# Dual6x09_CoCo2.net
KiCad netlist of a schematic drawn in EAGLE
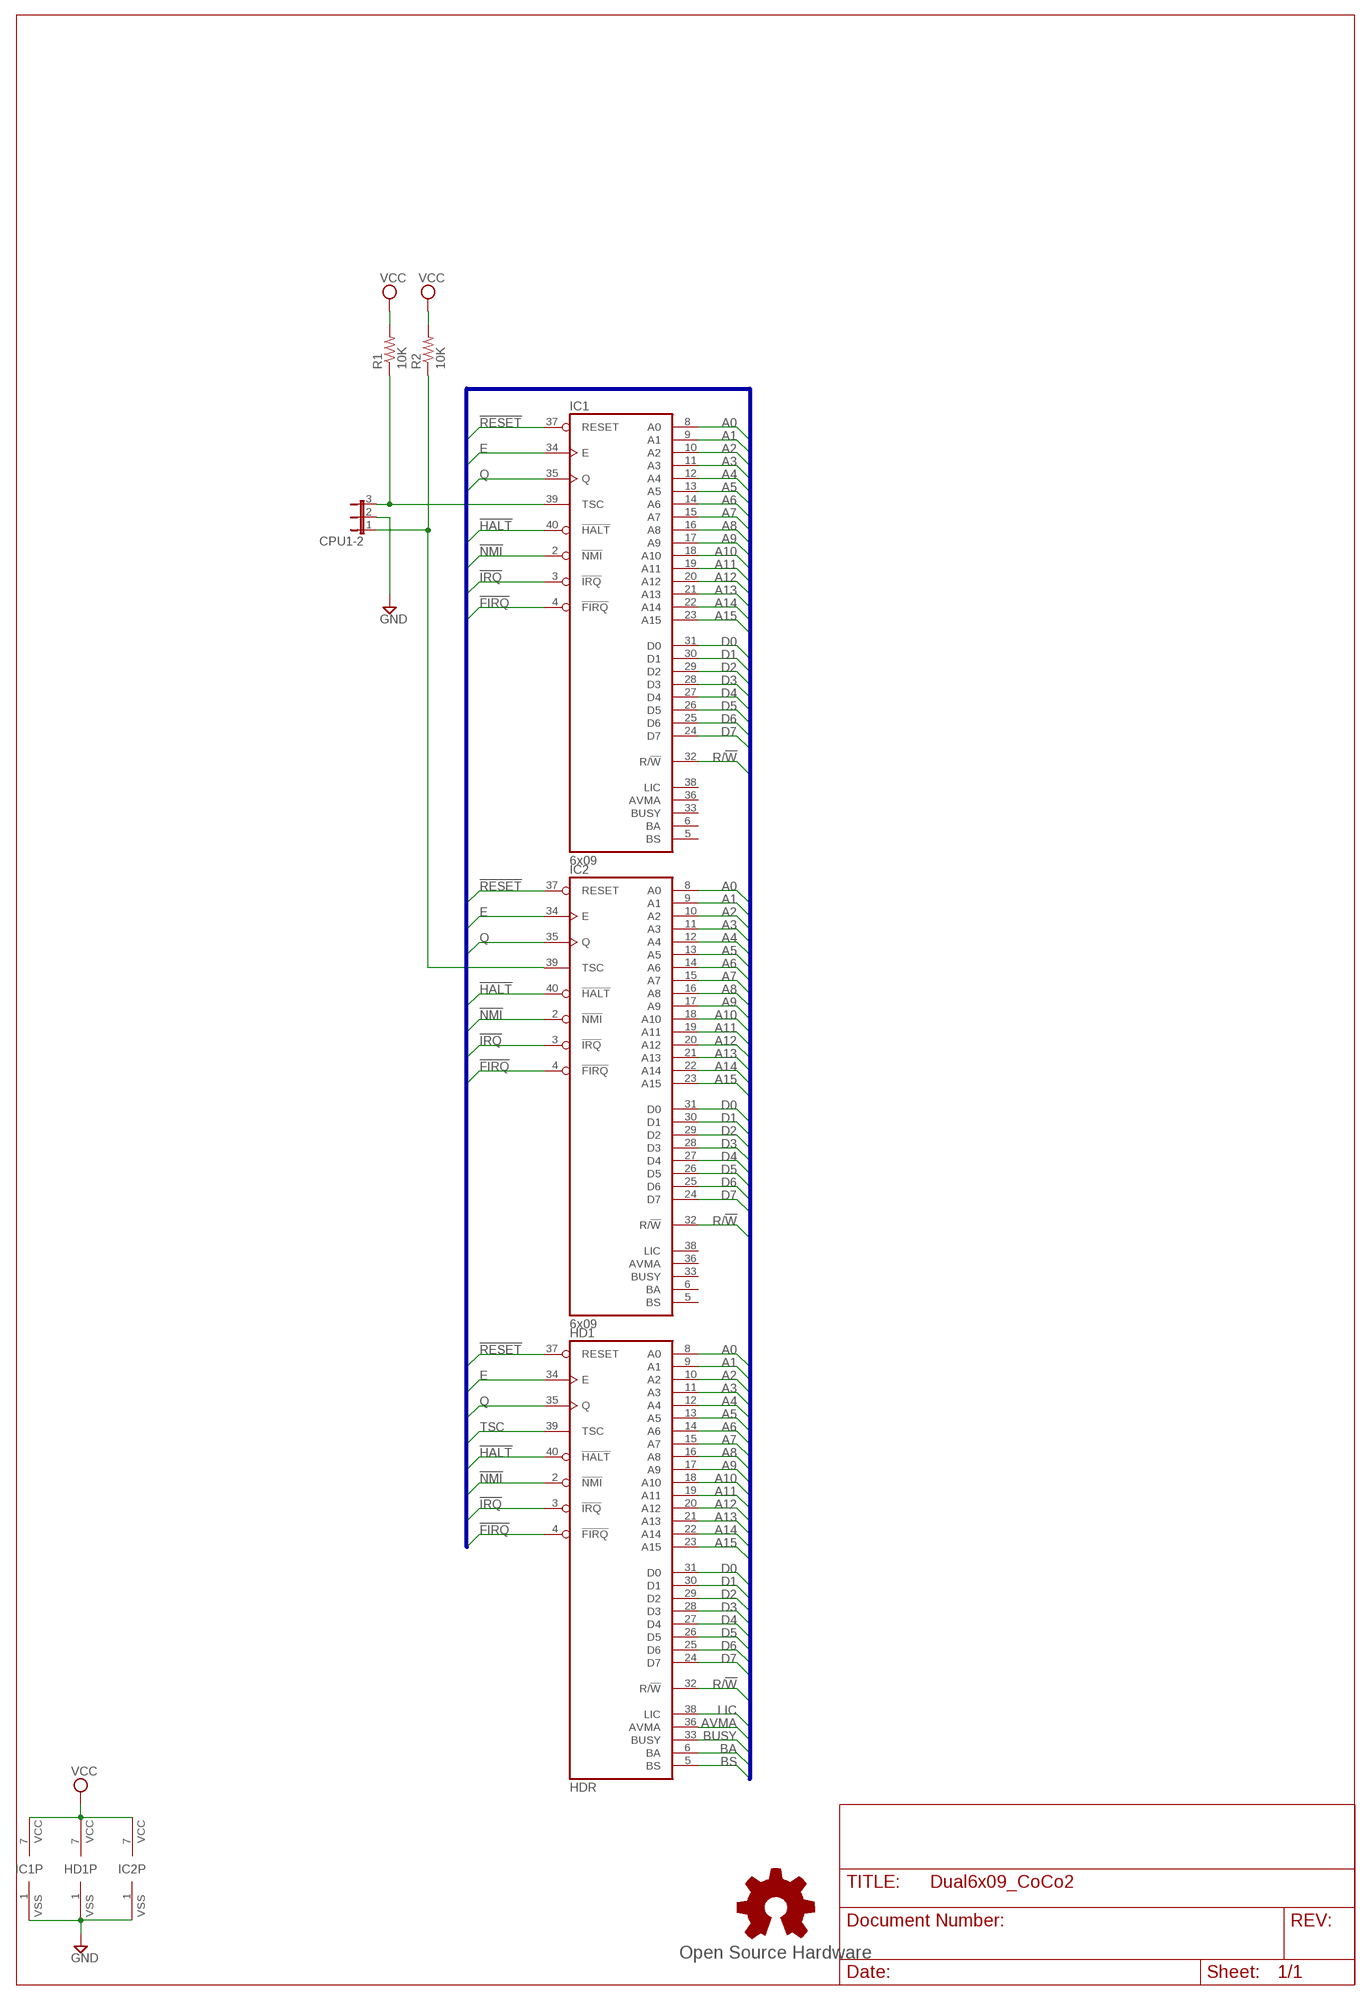
[diagram p0: schematic, sheet 1]

(export (version "E")
  (design (tool "Eeschema 10.0.6"))
  (components
    (comp (ref "CPU1-2")
      (value "JP2E")
      (footprint "eagle-import:JP2")
      (libsource (lib "eagle-import") (part "JP2E"))
    )
    (comp (ref "GOLD_ORB_SM1")
      (value "Open Source Hardware")
      (footprint "eagle-import:OSHW_5MM")
      (libsource (lib "eagle-import") (part "OSHWLOGOLOGO5MM"))
    )
    (comp (ref "HD1")
      (value "HDR")
      (footprint "eagle-import:DIL40-ROUNDPAD")
      (libsource (lib "eagle-import") (part "MC6809ER"))
    )
    (comp (ref "IC1")
      (value "6x09")
      (footprint "eagle-import:DIL40-ROUNDPAD")
      (libsource (lib "eagle-import") (part "MC6809ER"))
    )
    (comp (ref "IC2")
      (value "6x09")
      (footprint "eagle-import:DIL40-ROUNDPAD")
      (libsource (lib "eagle-import") (part "MC6809ER"))
    )
    (comp (ref "R1")
      (value "10K")
      (footprint "eagle-import:0204V")
      (libsource (lib "eagle-import") (part "R-US_0204/2V"))
    )
    (comp (ref "R2")
      (value "10K")
      (footprint "eagle-import:0204V")
      (libsource (lib "eagle-import") (part "R-US_0204/2V"))
    )
  )
  (nets
    (net (code "1") (name "/A0") (class "Default")
      (node (ref "HD1") (pin "8") (pinfunction "A0_8") (pintype "tri_state"))
      (node (ref "IC1") (pin "8") (pinfunction "A0_8") (pintype "tri_state"))
      (node (ref "IC2") (pin "8") (pinfunction "A0_8") (pintype "tri_state"))
    )
    (net (code "2") (name "/A1") (class "Default")
      (node (ref "HD1") (pin "9") (pinfunction "A1_9") (pintype "tri_state"))
      (node (ref "IC1") (pin "9") (pinfunction "A1_9") (pintype "tri_state"))
      (node (ref "IC2") (pin "9") (pinfunction "A1_9") (pintype "tri_state"))
    )
    (net (code "3") (name "/A2") (class "Default")
      (node (ref "HD1") (pin "10") (pinfunction "A2_10") (pintype "tri_state"))
      (node (ref "IC1") (pin "10") (pinfunction "A2_10") (pintype "tri_state"))
      (node (ref "IC2") (pin "10") (pinfunction "A2_10") (pintype "tri_state"))
    )
    (net (code "4") (name "/A3") (class "Default")
      (node (ref "HD1") (pin "11") (pinfunction "A3_11") (pintype "tri_state"))
      (node (ref "IC1") (pin "11") (pinfunction "A3_11") (pintype "tri_state"))
      (node (ref "IC2") (pin "11") (pinfunction "A3_11") (pintype "tri_state"))
    )
    (net (code "5") (name "/A4") (class "Default")
      (node (ref "HD1") (pin "12") (pinfunction "A4_12") (pintype "tri_state"))
      (node (ref "IC1") (pin "12") (pinfunction "A4_12") (pintype "tri_state"))
      (node (ref "IC2") (pin "12") (pinfunction "A4_12") (pintype "tri_state"))
    )
    (net (code "6") (name "/A5") (class "Default")
      (node (ref "HD1") (pin "13") (pinfunction "A5_13") (pintype "tri_state"))
      (node (ref "IC1") (pin "13") (pinfunction "A5_13") (pintype "tri_state"))
      (node (ref "IC2") (pin "13") (pinfunction "A5_13") (pintype "tri_state"))
    )
    (net (code "7") (name "/A6") (class "Default")
      (node (ref "HD1") (pin "14") (pinfunction "A6_14") (pintype "tri_state"))
      (node (ref "IC1") (pin "14") (pinfunction "A6_14") (pintype "tri_state"))
      (node (ref "IC2") (pin "14") (pinfunction "A6_14") (pintype "tri_state"))
    )
    (net (code "8") (name "/A7") (class "Default")
      (node (ref "HD1") (pin "15") (pinfunction "A7_15") (pintype "tri_state"))
      (node (ref "IC1") (pin "15") (pinfunction "A7_15") (pintype "tri_state"))
      (node (ref "IC2") (pin "15") (pinfunction "A7_15") (pintype "tri_state"))
    )
    (net (code "9") (name "/A8") (class "Default")
      (node (ref "HD1") (pin "16") (pinfunction "A8_16") (pintype "tri_state"))
      (node (ref "IC1") (pin "16") (pinfunction "A8_16") (pintype "tri_state"))
      (node (ref "IC2") (pin "16") (pinfunction "A8_16") (pintype "tri_state"))
    )
    (net (code "10") (name "/A9") (class "Default")
      (node (ref "HD1") (pin "17") (pinfunction "A9_17") (pintype "tri_state"))
      (node (ref "IC1") (pin "17") (pinfunction "A9_17") (pintype "tri_state"))
      (node (ref "IC2") (pin "17") (pinfunction "A9_17") (pintype "tri_state"))
    )
    (net (code "11") (name "/A10") (class "Default")
      (node (ref "HD1") (pin "18") (pinfunction "A10_18") (pintype "tri_state"))
      (node (ref "IC1") (pin "18") (pinfunction "A10_18") (pintype "tri_state"))
      (node (ref "IC2") (pin "18") (pinfunction "A10_18") (pintype "tri_state"))
    )
    (net (code "12") (name "/A11") (class "Default")
      (node (ref "HD1") (pin "19") (pinfunction "A11_19") (pintype "tri_state"))
      (node (ref "IC1") (pin "19") (pinfunction "A11_19") (pintype "tri_state"))
      (node (ref "IC2") (pin "19") (pinfunction "A11_19") (pintype "tri_state"))
    )
    (net (code "13") (name "/A12") (class "Default")
      (node (ref "HD1") (pin "20") (pinfunction "A12_20") (pintype "tri_state"))
      (node (ref "IC1") (pin "20") (pinfunction "A12_20") (pintype "tri_state"))
      (node (ref "IC2") (pin "20") (pinfunction "A12_20") (pintype "tri_state"))
    )
    (net (code "14") (name "/A13") (class "Default")
      (node (ref "HD1") (pin "21") (pinfunction "A13_21") (pintype "tri_state"))
      (node (ref "IC1") (pin "21") (pinfunction "A13_21") (pintype "tri_state"))
      (node (ref "IC2") (pin "21") (pinfunction "A13_21") (pintype "tri_state"))
    )
    (net (code "15") (name "/A14") (class "Default")
      (node (ref "HD1") (pin "22") (pinfunction "A14_22") (pintype "tri_state"))
      (node (ref "IC1") (pin "22") (pinfunction "A14_22") (pintype "tri_state"))
      (node (ref "IC2") (pin "22") (pinfunction "A14_22") (pintype "tri_state"))
    )
    (net (code "16") (name "/A15") (class "Default")
      (node (ref "HD1") (pin "23") (pinfunction "A15_23") (pintype "tri_state"))
      (node (ref "IC1") (pin "23") (pinfunction "A15_23") (pintype "tri_state"))
      (node (ref "IC2") (pin "23") (pinfunction "A15_23") (pintype "tri_state"))
    )
    (net (code "17") (name "/AVMA") (class "Default")
      (node (ref "HD1") (pin "36") (pinfunction "AVMA_36") (pintype "output"))
    )
    (net (code "18") (name "/BA") (class "Default")
      (node (ref "HD1") (pin "6") (pinfunction "BA_6") (pintype "output"))
    )
    (net (code "19") (name "/BS") (class "Default")
      (node (ref "HD1") (pin "5") (pinfunction "BS_5") (pintype "output"))
    )
    (net (code "20") (name "/BUSY") (class "Default")
      (node (ref "HD1") (pin "33") (pinfunction "BUSY_33") (pintype "output"))
    )
    (net (code "21") (name "/D0") (class "Default")
      (node (ref "HD1") (pin "31") (pinfunction "D0_31") (pintype "bidirectional"))
      (node (ref "IC1") (pin "31") (pinfunction "D0_31") (pintype "bidirectional"))
      (node (ref "IC2") (pin "31") (pinfunction "D0_31") (pintype "bidirectional"))
    )
    (net (code "22") (name "/D1") (class "Default")
      (node (ref "HD1") (pin "30") (pinfunction "D1_30") (pintype "bidirectional"))
      (node (ref "IC1") (pin "30") (pinfunction "D1_30") (pintype "bidirectional"))
      (node (ref "IC2") (pin "30") (pinfunction "D1_30") (pintype "bidirectional"))
    )
    (net (code "23") (name "/D2") (class "Default")
      (node (ref "HD1") (pin "29") (pinfunction "D2_29") (pintype "bidirectional"))
      (node (ref "IC1") (pin "29") (pinfunction "D2_29") (pintype "bidirectional"))
      (node (ref "IC2") (pin "29") (pinfunction "D2_29") (pintype "bidirectional"))
    )
    (net (code "24") (name "/D3") (class "Default")
      (node (ref "HD1") (pin "28") (pinfunction "D3_28") (pintype "bidirectional"))
      (node (ref "IC1") (pin "28") (pinfunction "D3_28") (pintype "bidirectional"))
      (node (ref "IC2") (pin "28") (pinfunction "D3_28") (pintype "bidirectional"))
    )
    (net (code "25") (name "/D4") (class "Default")
      (node (ref "HD1") (pin "27") (pinfunction "D4_27") (pintype "bidirectional"))
      (node (ref "IC1") (pin "27") (pinfunction "D4_27") (pintype "bidirectional"))
      (node (ref "IC2") (pin "27") (pinfunction "D4_27") (pintype "bidirectional"))
    )
    (net (code "26") (name "/D5") (class "Default")
      (node (ref "HD1") (pin "26") (pinfunction "D5_26") (pintype "bidirectional"))
      (node (ref "IC1") (pin "26") (pinfunction "D5_26") (pintype "bidirectional"))
      (node (ref "IC2") (pin "26") (pinfunction "D5_26") (pintype "bidirectional"))
    )
    (net (code "27") (name "/D6") (class "Default")
      (node (ref "HD1") (pin "25") (pinfunction "D6_25") (pintype "bidirectional"))
      (node (ref "IC1") (pin "25") (pinfunction "D6_25") (pintype "bidirectional"))
      (node (ref "IC2") (pin "25") (pinfunction "D6_25") (pintype "bidirectional"))
    )
    (net (code "28") (name "/D7") (class "Default")
      (node (ref "HD1") (pin "24") (pinfunction "D7_24") (pintype "bidirectional"))
      (node (ref "IC1") (pin "24") (pinfunction "D7_24") (pintype "bidirectional"))
      (node (ref "IC2") (pin "24") (pinfunction "D7_24") (pintype "bidirectional"))
    )
    (net (code "29") (name "/E") (class "Default")
      (node (ref "HD1") (pin "34") (pinfunction "E_34") (pintype "input"))
      (node (ref "IC1") (pin "34") (pinfunction "E_34") (pintype "input"))
      (node (ref "IC2") (pin "34") (pinfunction "E_34") (pintype "input"))
    )
    (net (code "30") (name "/LIC") (class "Default")
      (node (ref "HD1") (pin "38") (pinfunction "LIC_38") (pintype "output"))
    )
    (net (code "31") (name "/Q") (class "Default")
      (node (ref "HD1") (pin "35") (pinfunction "Q_35") (pintype "input"))
      (node (ref "IC1") (pin "35") (pinfunction "Q_35") (pintype "input"))
      (node (ref "IC2") (pin "35") (pinfunction "Q_35") (pintype "input"))
    )
    (net (code "32") (name "/R{slash}~{W}") (class "Default")
      (node (ref "HD1") (pin "32") (pinfunction "R/~{W}_32") (pintype "output"))
      (node (ref "IC1") (pin "32") (pinfunction "R/~{W}_32") (pintype "output"))
      (node (ref "IC2") (pin "32") (pinfunction "R/~{W}_32") (pintype "output"))
    )
    (net (code "33") (name "/TSC") (class "Default")
      (node (ref "HD1") (pin "39") (pinfunction "TSC_39") (pintype "open_collector"))
    )
    (net (code "34") (name "/~{FIRQ}") (class "Default")
      (node (ref "HD1") (pin "4") (pinfunction "~{FIRQ}_4") (pintype "open_collector"))
      (node (ref "IC1") (pin "4") (pinfunction "~{FIRQ}_4") (pintype "open_collector"))
      (node (ref "IC2") (pin "4") (pinfunction "~{FIRQ}_4") (pintype "open_collector"))
    )
    (net (code "35") (name "/~{HALT}") (class "Default")
      (node (ref "HD1") (pin "40") (pinfunction "~{HALT}_40") (pintype "open_collector"))
      (node (ref "IC1") (pin "40") (pinfunction "~{HALT}_40") (pintype "open_collector"))
      (node (ref "IC2") (pin "40") (pinfunction "~{HALT}_40") (pintype "open_collector"))
    )
    (net (code "36") (name "/~{IRQ}") (class "Default")
      (node (ref "HD1") (pin "3") (pinfunction "~{IRQ}_3") (pintype "open_collector"))
      (node (ref "IC1") (pin "3") (pinfunction "~{IRQ}_3") (pintype "open_collector"))
      (node (ref "IC2") (pin "3") (pinfunction "~{IRQ}_3") (pintype "open_collector"))
    )
    (net (code "37") (name "/~{NMI}") (class "Default")
      (node (ref "HD1") (pin "2") (pinfunction "~{NMI}_2") (pintype "open_collector"))
      (node (ref "IC1") (pin "2") (pinfunction "~{NMI}_2") (pintype "open_collector"))
      (node (ref "IC2") (pin "2") (pinfunction "~{NMI}_2") (pintype "open_collector"))
    )
    (net (code "38") (name "/~{RESET}") (class "Default")
      (node (ref "HD1") (pin "37") (pinfunction "RESET_37") (pintype "input"))
      (node (ref "IC1") (pin "37") (pinfunction "RESET_37") (pintype "input"))
      (node (ref "IC2") (pin "37") (pinfunction "RESET_37") (pintype "input"))
    )
    (net (code "39") (name "GND") (class "Default")
      (node (ref "CPU1-2") (pin "2") (pinfunction "2_2") (pintype "passive"))
      (node (ref "HD1") (pin "1") (pinfunction "VSS_1") (pintype "power_in"))
      (node (ref "IC1") (pin "1") (pinfunction "VSS_1") (pintype "power_in"))
      (node (ref "IC2") (pin "1") (pinfunction "VSS_1") (pintype "power_in"))
    )
    (net (code "40") (name "Net-(IC1A-TSC)") (class "Default")
      (node (ref "CPU1-2") (pin "3") (pinfunction "3_3") (pintype "passive"))
      (node (ref "IC1") (pin "39") (pinfunction "TSC_39") (pintype "open_collector"))
      (node (ref "R1") (pin "1") (pinfunction "1_1") (pintype "passive"))
    )
    (net (code "41") (name "Net-(IC2A-TSC)") (class "Default")
      (node (ref "CPU1-2") (pin "1") (pinfunction "1_1") (pintype "passive"))
      (node (ref "IC2") (pin "39") (pinfunction "TSC_39") (pintype "open_collector"))
      (node (ref "R2") (pin "1") (pinfunction "1_1") (pintype "passive"))
    )
    (net (code "42") (name "VCC") (class "Default")
      (node (ref "HD1") (pin "7") (pinfunction "VCC_7") (pintype "power_in"))
      (node (ref "IC1") (pin "7") (pinfunction "VCC_7") (pintype "power_in"))
      (node (ref "IC2") (pin "7") (pinfunction "VCC_7") (pintype "power_in"))
      (node (ref "R1") (pin "2") (pinfunction "2_2") (pintype "passive"))
      (node (ref "R2") (pin "2") (pinfunction "2_2") (pintype "passive"))
    )
    (net (code "43") (name "unconnected-(IC1A-AVMA-Pad36)") (class "Default")
      (node (ref "IC1") (pin "36") (pinfunction "AVMA_36") (pintype "output"))
    )
    (net (code "44") (name "unconnected-(IC1A-BA-Pad6)") (class "Default")
      (node (ref "IC1") (pin "6") (pinfunction "BA_6") (pintype "output"))
    )
    (net (code "45") (name "unconnected-(IC1A-BS-Pad5)") (class "Default")
      (node (ref "IC1") (pin "5") (pinfunction "BS_5") (pintype "output"))
    )
    (net (code "46") (name "unconnected-(IC1A-BUSY-Pad33)") (class "Default")
      (node (ref "IC1") (pin "33") (pinfunction "BUSY_33") (pintype "output"))
    )
    (net (code "47") (name "unconnected-(IC1A-LIC-Pad38)") (class "Default")
      (node (ref "IC1") (pin "38") (pinfunction "LIC_38") (pintype "output"))
    )
    (net (code "48") (name "unconnected-(IC2A-AVMA-Pad36)") (class "Default")
      (node (ref "IC2") (pin "36") (pinfunction "AVMA_36") (pintype "output"))
    )
    (net (code "49") (name "unconnected-(IC2A-BA-Pad6)") (class "Default")
      (node (ref "IC2") (pin "6") (pinfunction "BA_6") (pintype "output"))
    )
    (net (code "50") (name "unconnected-(IC2A-BS-Pad5)") (class "Default")
      (node (ref "IC2") (pin "5") (pinfunction "BS_5") (pintype "output"))
    )
    (net (code "51") (name "unconnected-(IC2A-BUSY-Pad33)") (class "Default")
      (node (ref "IC2") (pin "33") (pinfunction "BUSY_33") (pintype "output"))
    )
    (net (code "52") (name "unconnected-(IC2A-LIC-Pad38)") (class "Default")
      (node (ref "IC2") (pin "38") (pinfunction "LIC_38") (pintype "output"))
    )
  )
)
